# USBtoTTL.net
KiCad netlist of a schematic drawn in Altium Designer
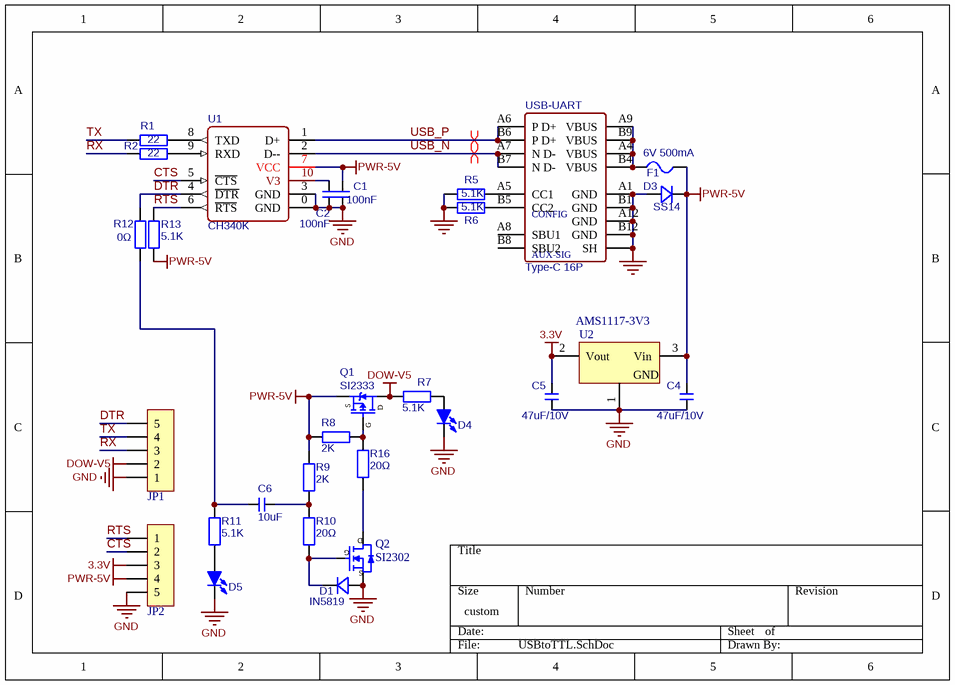
[diagram p0: USBtoTTL.SchDoc]

(export (version "E")
  (design (tool "Eeschema 10.0.6"))
  (components
    (comp (ref "C1")
      (value "100nF")
      (footprint "C 0402_L")
      (description "无极性贴片多层陶瓷电容器")
      (fields (field (name "版权归属") "源创客"))
      (libsource (lib "0.1 - 电阻-电容-电感") (part "C-MLCC"))
    )
    (comp (ref "C2")
      (value "100nF")
      (footprint "C 0402_L")
      (description "无极性贴片多层陶瓷电容器")
      (fields (field (name "版权归属") "源创客"))
      (libsource (lib "0.1 - 电阻-电容-电感") (part "C-MLCC"))
    )
    (comp (ref "C4")
      (value "47uF/10V")
      (footprint "C 0805_L")
      (description "无极性贴片多层陶瓷电容器")
      (fields (field (name "版权归属") "源创客"))
      (libsource (lib "0.1 - 电阻-电容-电感") (part "C-MLCC"))
    )
    (comp (ref "C5")
      (value "47uF/10V")
      (footprint "C 0805_L")
      (description "无极性贴片多层陶瓷电容器")
      (fields (field (name "版权归属") "源创客"))
      (libsource (lib "0.1 - 电阻-电容-电感") (part "C-MLCC"))
    )
    (comp (ref "C6")
      (value "10uF")
      (footprint "C 0805_L")
      (description "无极性贴片多层陶瓷电容器")
      (fields (field (name "版权归属") "源创客"))
      (libsource (lib "0.1 - 电阻-电容-电感") (part "C-MLCC"))
    )
    (comp (ref "D1")
      (value "IN5819")
      (footprint "SOD-523")
      (description "快恢复开关二极管-所有封装")
      (fields (field (name "版权归属") "源创客"))
      (libsource (lib "0.2 - 二极管-整流桥") (part "1N4948"))
    )
    (comp (ref "D3")
      (value "SS14")
      (footprint "SOD-323")
      (description "快恢复开关二极管-所有封装")
      (fields (field (name "版权归属") "源创客"))
      (libsource (lib "0.2 - 二极管-整流桥") (part "1N4948"))
    )
    (comp (ref "D4")
      (value "BLUE")
      (footprint "LED 0603_M")
      (description "贴片LED")
      (fields (field (name "版权归属") "封装库来自淘宝 ID：黄晶宝石"))
      (libsource (lib "0.3 - LED发光二极管") (part "LED-SMD"))
    )
    (comp (ref "D5")
      (value "BLUE")
      (footprint "LED 0603_M")
      (description "贴片LED")
      (fields (field (name "版权归属") "封装库来自淘宝 ID：黄晶宝石"))
      (libsource (lib "0.3 - LED发光二极管") (part "LED-SMD"))
    )
    (comp (ref "F1")
      (value "6V 500mA")
      (footprint "FU 0603")
      (description "贴片保险丝")
      (fields (field (name "Comment") "BSMD0603-050-6V") (field (name "版权归属") "封装库来自淘宝卖家 ID：黄晶宝石"))
      (libsource (lib "2.0 - 保险丝-晶振-光耦-跳线") (part "FU"))
    )
    (comp (ref "JP1")
      (value "HDR-1X5")
      (footprint "HDR2.54-WS-5P")
      (description "5P接插件")
      (fields (field (name "版权归属") "封装库来自淘宝 ID：黄晶宝石"))
      (libsource (lib "") (part "Header 5_1"))
    )
    (comp (ref "JP2")
      (value "HDR-1X5")
      (footprint "HDR2.54-WS-5P")
      (description "5P接插件")
      (fields (field (name "版权归属") "封装库来自淘宝 ID：黄晶宝石"))
      (libsource (lib "5.4 - 接插件-脚距2.54 (100mil) ") (part "Header 5"))
    )
    (comp (ref "Q1")
      (value "SI2333")
      (footprint "SOT23-3L")
      (description "P沟道 12V/6A")
      (fields (field (name "版权归属") "源创客"))
      (libsource (lib "0.5 - 场效应管-可控硅") (part "CJ2333"))
    )
    (comp (ref "Q2")
      (value "SI2302")
      (footprint "SOT23-3L")
      (description "N沟道 20V/3A")
      (fields (field (name "版权归属") "源创客"))
      (libsource (lib "0.5 - 场效应管-可控硅") (part "SI2302"))
    )
    (comp (ref "R1")
      (value "22")
      (footprint "R 0402_L")
      (description "贴片电阻")
      (fields (field (name "版权归属") "来自淘宝 ID：黄晶宝石"))
      (libsource (lib "0.1 - 电阻-电容-电感") (part "RES"))
    )
    (comp (ref "R2")
      (value "22")
      (footprint "R 0402_L")
      (description "贴片电阻")
      (fields (field (name "版权归属") "来自淘宝 ID：黄晶宝石"))
      (libsource (lib "0.1 - 电阻-电容-电感") (part "RES"))
    )
    (comp (ref "R5")
      (value "5.1K")
      (footprint "R 0402_L")
      (description "贴片电阻")
      (fields (field (name "版权归属") "来自淘宝 ID：黄晶宝石"))
      (libsource (lib "0.1 - 电阻-电容-电感") (part "RES"))
    )
    (comp (ref "R6")
      (value "5.1K")
      (footprint "R 0402_L")
      (description "贴片电阻")
      (fields (field (name "版权归属") "来自淘宝 ID：黄晶宝石"))
      (libsource (lib "0.1 - 电阻-电容-电感") (part "RES"))
    )
    (comp (ref "R7")
      (value "5.1K")
      (footprint "R 0402_L")
      (description "贴片电阻")
      (fields (field (name "版权归属") "来自淘宝 ID：黄晶宝石"))
      (libsource (lib "0.1 - 电阻-电容-电感") (part "RES"))
    )
    (comp (ref "R8")
      (value "2K")
      (footprint "R 0402_L")
      (description "贴片电阻")
      (fields (field (name "版权归属") "来自淘宝 ID：黄晶宝石"))
      (libsource (lib "0.1 - 电阻-电容-电感") (part "RES"))
    )
    (comp (ref "R9")
      (value "2K")
      (footprint "R 0402_L")
      (description "贴片电阻")
      (fields (field (name "版权归属") "来自淘宝 ID：黄晶宝石"))
      (libsource (lib "0.1 - 电阻-电容-电感") (part "RES"))
    )
    (comp (ref "R10")
      (value "20Ω")
      (footprint "R 0402_L")
      (description "贴片电阻")
      (fields (field (name "版权归属") "来自淘宝 ID：黄晶宝石"))
      (libsource (lib "0.1 - 电阻-电容-电感") (part "RES"))
    )
    (comp (ref "R11")
      (value "5.1K")
      (footprint "R 0402_L")
      (description "贴片电阻")
      (fields (field (name "版权归属") "来自淘宝 ID：黄晶宝石"))
      (libsource (lib "0.1 - 电阻-电容-电感") (part "RES"))
    )
    (comp (ref "R12")
      (value "0Ω")
      (footprint "R 0402_L")
      (description "贴片电阻")
      (fields (field (name "版权归属") "来自淘宝 ID：黄晶宝石"))
      (libsource (lib "0.1 - 电阻-电容-电感") (part "RES"))
    )
    (comp (ref "R13")
      (value "5.1K")
      (footprint "R 0402_L")
      (description "贴片电阻")
      (fields (field (name "版权归属") "来自淘宝 ID：黄晶宝石"))
      (libsource (lib "0.1 - 电阻-电容-电感") (part "RES"))
    )
    (comp (ref "R16")
      (value "20Ω")
      (footprint "R 0402_L")
      (description "贴片电阻")
      (fields (field (name "版权归属") "来自淘宝 ID：黄晶宝石"))
      (libsource (lib "0.1 - 电阻-电容-电感") (part "RES"))
    )
    (comp (ref "U1")
      (value "CH340K")
      (footprint "ESSOP-10_L")
      (description "USB转串口")
      (fields (field (name "BOM_MANUFACTURER PART") "CH340C") (field (name "BOM_SUPPLIER PART") "C84681"))
      (libsource (lib "1.0 - 通信总线芯片") (part "CH340K"))
    )
    (comp (ref "U2")
      (value "AMS1117-3V3")
      (footprint "SOT89_L")
      (description "三端稳压")
      (libsource (lib "1.1 - 电源类芯片") (part "AMS1117"))
    )
    (comp (ref "USB-UART")
      (value "Type-C 16P")
      (footprint "USB-C/S_16P_M")
      (description "TYPE-C 16Pin母座")
      (libsource (lib "0.8 - 以太网-音频-USB插座") (part "USB-C/S 16P"))
    )
  )
  (nets
    (net (code "1") (name "/CTS") (class "Default")
      (node (ref "JP2") (pin "2") (pinfunction "2_2") (pintype "passive"))
      (node (ref "U1") (pin "5") (pinfunction "~{CTS}_5") (pintype "input"))
    )
    (net (code "2") (name "/DTR") (class "Default")
      (node (ref "JP1") (pin "5") (pinfunction "5_5") (pintype "passive"))
      (node (ref "R12") (pin "1") (pinfunction "1_1") (pintype "passive"))
      (node (ref "U1") (pin "4") (pinfunction "~{DTR}_4") (pintype "output"))
    )
    (net (code "3") (name "/RTS") (class "Default")
      (node (ref "JP2") (pin "1") (pinfunction "1_1") (pintype "passive"))
      (node (ref "R13") (pin "1") (pinfunction "1_1") (pintype "passive"))
      (node (ref "U1") (pin "6") (pinfunction "~{RTS}_6") (pintype "output"))
    )
    (net (code "4") (name "/RX") (class "Default")
      (node (ref "JP1") (pin "3") (pinfunction "3_3") (pintype "passive"))
      (node (ref "R2") (pin "1") (pinfunction "1_1") (pintype "passive"))
    )
    (net (code "5") (name "/TX") (class "Default")
      (node (ref "JP1") (pin "4") (pinfunction "4_4") (pintype "passive"))
      (node (ref "R1") (pin "1") (pinfunction "1_1") (pintype "passive"))
    )
    (net (code "6") (name "/USB_N") (class "Default")
      (node (ref "U1") (pin "2") (pinfunction "D--_2") (pintype "passive"))
      (node (ref "USB-UART") (pin "A7") (pinfunction "N_D-_A7") (pintype "passive"))
      (node (ref "USB-UART") (pin "B7") (pinfunction "N_D-_B7") (pintype "passive"))
    )
    (net (code "7") (name "/USB_P") (class "Default")
      (node (ref "U1") (pin "1") (pinfunction "D+_1") (pintype "passive"))
      (node (ref "USB-UART") (pin "A6") (pinfunction "P_D+_A6") (pintype "passive"))
      (node (ref "USB-UART") (pin "B6") (pinfunction "P_D+_B6") (pintype "passive"))
    )
    (net (code "8") (name "3.3V") (class "Default")
      (node (ref "C5") (pin "2") (pinfunction "K_2") (pintype "passive"))
      (node (ref "JP2") (pin "3") (pinfunction "3_3") (pintype "passive"))
      (node (ref "U2") (pin "2") (pinfunction "Vout_2") (pintype "passive"))
    )
    (net (code "9") (name "DOW-V5") (class "Default")
      (node (ref "JP1") (pin "2") (pinfunction "2_2") (pintype "passive"))
      (node (ref "Q1") (pin "3") (pinfunction "D_3") (pintype "passive"))
      (node (ref "R7") (pin "2") (pinfunction "2_2") (pintype "passive"))
    )
    (net (code "10") (name "GND") (class "Default")
      (node (ref "C1") (pin "1") (pinfunction "A_1") (pintype "passive"))
      (node (ref "C2") (pin "1") (pinfunction "A_1") (pintype "passive"))
      (node (ref "C4") (pin "1") (pinfunction "A_1") (pintype "passive"))
      (node (ref "C5") (pin "1") (pinfunction "A_1") (pintype "passive"))
      (node (ref "D1") (pin "1") (pinfunction "1_1") (pintype "passive"))
      (node (ref "D3") (pin "1") (pinfunction "1_1") (pintype "passive"))
      (node (ref "D4") (pin "2") (pinfunction "K_2") (pintype "passive"))
      (node (ref "D5") (pin "2") (pinfunction "K_2") (pintype "passive"))
      (node (ref "JP1") (pin "1") (pinfunction "1_1") (pintype "passive"))
      (node (ref "JP2") (pin "5") (pinfunction "5_5") (pintype "passive"))
      (node (ref "Q2") (pin "2") (pinfunction "S_2") (pintype "passive"))
      (node (ref "R5") (pin "1") (pinfunction "1_1") (pintype "passive"))
      (node (ref "R6") (pin "1") (pinfunction "1_1") (pintype "passive"))
      (node (ref "U1") (pin "0") (pinfunction "GND_0") (pintype "passive"))
      (node (ref "U1") (pin "3") (pinfunction "GND_3") (pintype "passive"))
      (node (ref "U2") (pin "1") (pinfunction "GND_1") (pintype "passive"))
      (node (ref "USB-UART") (pin "1") (pinfunction "SH_1") (pintype "passive"))
      (node (ref "USB-UART") (pin "A1") (pinfunction "GND_A1") (pintype "passive"))
      (node (ref "USB-UART") (pin "A12") (pinfunction "GND_A12") (pintype "passive"))
      (node (ref "USB-UART") (pin "B1") (pinfunction "GND_B1") (pintype "passive"))
      (node (ref "USB-UART") (pin "B12") (pinfunction "GND_B12") (pintype "passive"))
    )
    (net (code "11") (name "Net-(C2-K)") (class "Default")
      (node (ref "C2") (pin "2") (pinfunction "K_2") (pintype "passive"))
      (node (ref "U1") (pin "10") (pinfunction "V3_10") (pintype "power_in"))
    )
    (net (code "12") (name "Net-(C6-A)") (class "Default")
      (node (ref "C6") (pin "1") (pinfunction "A_1") (pintype "passive"))
      (node (ref "R10") (pin "1") (pinfunction "1_1") (pintype "passive"))
      (node (ref "R9") (pin "2") (pinfunction "2_2") (pintype "passive"))
    )
    (net (code "13") (name "Net-(C6-K)") (class "Default")
      (node (ref "C6") (pin "2") (pinfunction "K_2") (pintype "passive"))
      (node (ref "R11") (pin "1") (pinfunction "1_1") (pintype "passive"))
      (node (ref "R12") (pin "2") (pinfunction "2_2") (pintype "passive"))
    )
    (net (code "14") (name "Net-(D4-A)") (class "Default")
      (node (ref "D4") (pin "1") (pinfunction "A_1") (pintype "passive"))
      (node (ref "R7") (pin "1") (pinfunction "1_1") (pintype "passive"))
    )
    (net (code "15") (name "Net-(D5-A)") (class "Default")
      (node (ref "D5") (pin "1") (pinfunction "A_1") (pintype "passive"))
      (node (ref "R11") (pin "2") (pinfunction "2_2") (pintype "passive"))
    )
    (net (code "16") (name "Net-(F1-Pad1)") (class "Default")
      (node (ref "F1") (pin "1") (pinfunction "1_1") (pintype "passive"))
      (node (ref "USB-UART") (pin "A4") (pinfunction "VBUS_A4") (pintype "passive"))
      (node (ref "USB-UART") (pin "A9") (pinfunction "VBUS_A9") (pintype "passive"))
      (node (ref "USB-UART") (pin "B4") (pinfunction "VBUS_B4") (pintype "passive"))
      (node (ref "USB-UART") (pin "B9") (pinfunction "VBUS_B9") (pintype "passive"))
    )
    (net (code "17") (name "Net-(Q1-G)") (class "Default")
      (node (ref "Q1") (pin "1") (pinfunction "G_1") (pintype "passive"))
      (node (ref "R16") (pin "1") (pinfunction "1_1") (pintype "passive"))
      (node (ref "R8") (pin "2") (pinfunction "2_2") (pintype "passive"))
    )
    (net (code "18") (name "Net-(Q2-D)") (class "Default")
      (node (ref "Q2") (pin "3") (pinfunction "D_3") (pintype "passive"))
      (node (ref "R16") (pin "2") (pinfunction "2_2") (pintype "passive"))
    )
    (net (code "19") (name "Net-(Q2-G)") (class "Default")
      (node (ref "D1") (pin "2") (pinfunction "2_2") (pintype "passive"))
      (node (ref "Q2") (pin "1") (pinfunction "G_1") (pintype "passive"))
      (node (ref "R10") (pin "2") (pinfunction "2_2") (pintype "passive"))
    )
    (net (code "20") (name "Net-(U1-RXD)") (class "Default")
      (node (ref "R2") (pin "2") (pinfunction "2_2") (pintype "passive"))
      (node (ref "U1") (pin "9") (pinfunction "RXD_9") (pintype "input"))
    )
    (net (code "21") (name "Net-(U1-TXD)") (class "Default")
      (node (ref "R1") (pin "2") (pinfunction "2_2") (pintype "passive"))
      (node (ref "U1") (pin "8") (pinfunction "TXD_8") (pintype "output"))
    )
    (net (code "22") (name "Net-(USB-UART-CC1)") (class "Default")
      (node (ref "R5") (pin "2") (pinfunction "2_2") (pintype "passive"))
      (node (ref "USB-UART") (pin "A5") (pinfunction "CC1_A5") (pintype "passive"))
    )
    (net (code "23") (name "Net-(USB-UART-CC2)") (class "Default")
      (node (ref "R6") (pin "2") (pinfunction "2_2") (pintype "passive"))
      (node (ref "USB-UART") (pin "B5") (pinfunction "CC2_B5") (pintype "passive"))
    )
    (net (code "24") (name "PWR-5V") (class "Default")
      (node (ref "C1") (pin "2") (pinfunction "K_2") (pintype "passive"))
      (node (ref "C4") (pin "2") (pinfunction "K_2") (pintype "passive"))
      (node (ref "D3") (pin "2") (pinfunction "2_2") (pintype "passive"))
      (node (ref "F1") (pin "2") (pinfunction "2_2") (pintype "passive"))
      (node (ref "JP2") (pin "4") (pinfunction "4_4") (pintype "passive"))
      (node (ref "Q1") (pin "2") (pinfunction "S_2") (pintype "passive"))
      (node (ref "R13") (pin "2") (pinfunction "2_2") (pintype "passive"))
      (node (ref "R8") (pin "1") (pinfunction "1_1") (pintype "passive"))
      (node (ref "R9") (pin "1") (pinfunction "1_1") (pintype "passive"))
      (node (ref "U1") (pin "7") (pinfunction "VCC_7") (pintype "power_in"))
      (node (ref "U2") (pin "3") (pinfunction "Vin_3") (pintype "passive"))
    )
    (net (code "25") (name "unconnected-(USB-UART-SBU1-PadA8)") (class "Default")
      (node (ref "USB-UART") (pin "A8") (pinfunction "SBU1_A8") (pintype "passive"))
    )
    (net (code "26") (name "unconnected-(USB-UART-SBU2-PadB8)") (class "Default")
      (node (ref "USB-UART") (pin "B8") (pinfunction "SBU2_B8") (pintype "passive"))
    )
  )
)
